# Sheet1.net
KiCad netlist of a schematic drawn in Altium Designer
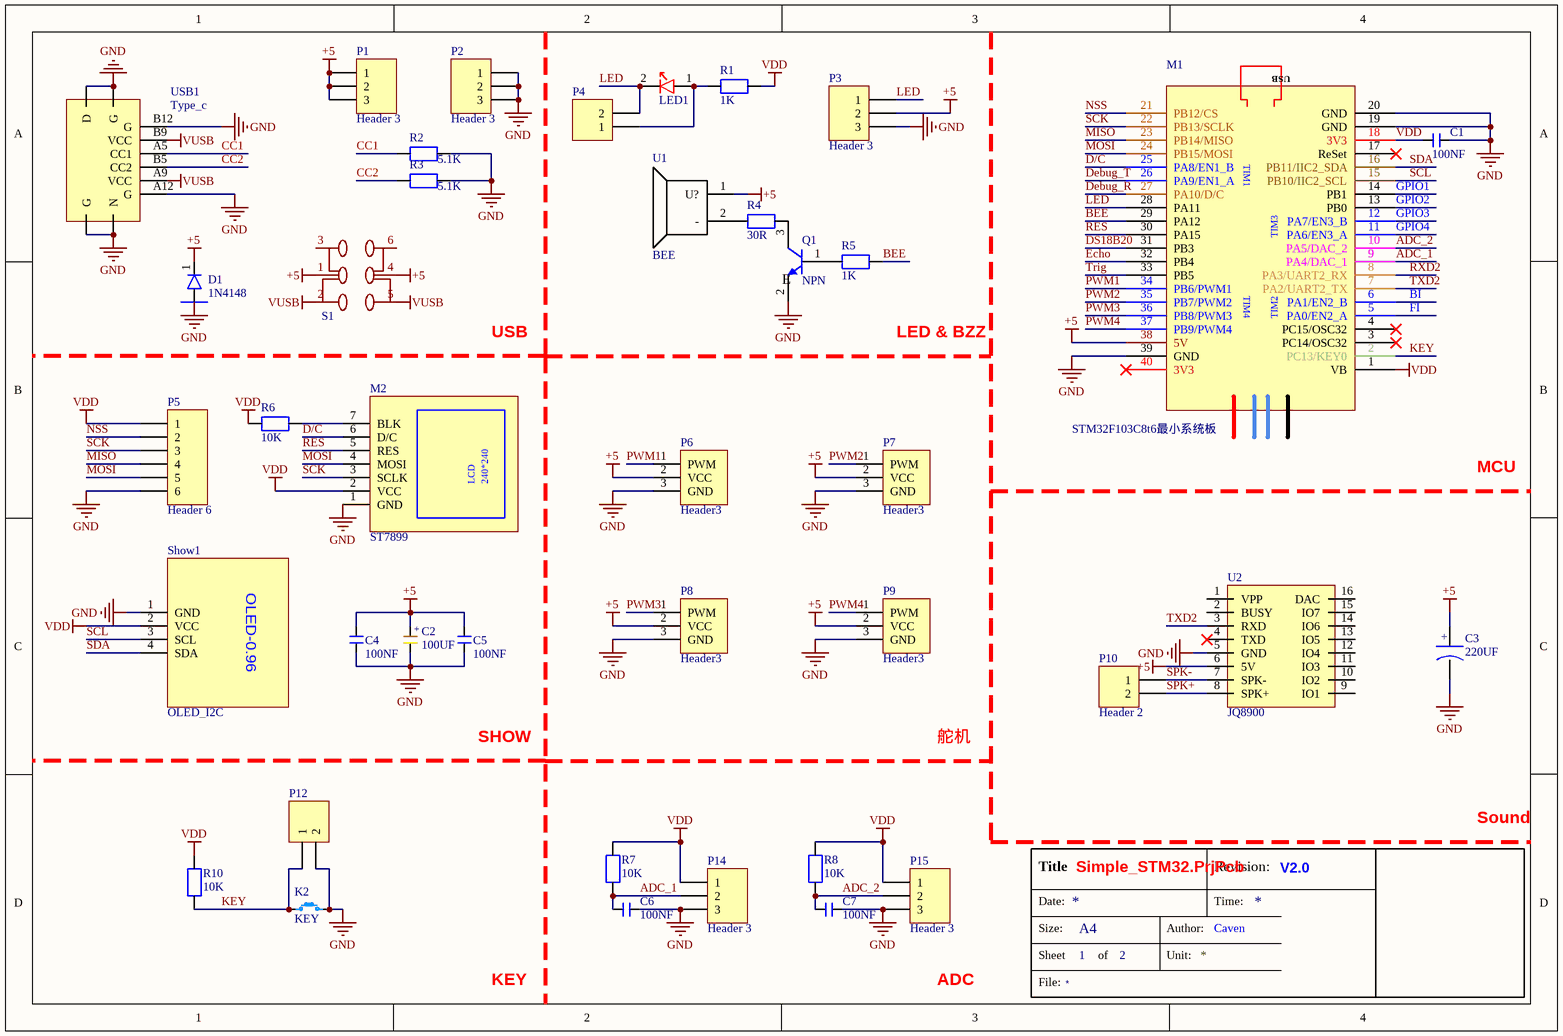
[diagram p0: Sheet1.SchDoc]

(export (version "E")
  (design (tool "Eeschema 10.0.6"))
  (components
    (comp (ref "C1")
      (value "100NF")
      (footprint "CAP_0603")
      (description "CAP  12~50V")
      (libsource (lib "User") (part "CAP"))
    )
    (comp (ref "C2")
      (value "100UF")
      (footprint "CAP_3216_A")
      (description "CAP  6~12V  钽电容")
      (libsource (lib "User") (part "CAP_TA"))
    )
    (comp (ref "C3")
      (value "220UF")
      (footprint "CAP_PR_2.5_6.3_RA")
      (description "CAP 12V ~ 50V   电解电容")
      (libsource (lib "User") (part "CAP_BIG"))
    )
    (comp (ref "C4")
      (value "100NF")
      (footprint "CAP_0603")
      (description "CAP  12~50V")
      (libsource (lib "User") (part "CAP"))
    )
    (comp (ref "C5")
      (value "100NF")
      (footprint "CAP_0603")
      (description "CAP  12~50V")
      (libsource (lib "User") (part "CAP"))
    )
    (comp (ref "C6")
      (value "100NF")
      (footprint "CAP_0603")
      (description "CAP  12~50V")
      (libsource (lib "User") (part "CAP"))
    )
    (comp (ref "C7")
      (value "100NF")
      (footprint "CAP_0603")
      (description "CAP  12~50V")
      (libsource (lib "User") (part "CAP"))
    )
    (comp (ref "D1")
      (value "1N4148")
      (footprint "Diode_DO35")
      (description "Diode_肖特基/二极管 \r\n直插")
      (libsource (lib "User") (part "Diode-DO"))
    )
    (comp (ref "K2")
      (value "KEY")
      (footprint "SW_PB_3X6")
      (description "Key")
      (libsource (lib "User") (part "KEY"))
    )
    (comp (ref "LED1")
      (value "LED_R/G/B/Y")
      (footprint "LED_5MM")
      (description "LED")
      (libsource (lib "User") (part "LED"))
    )
    (comp (ref "M1")
      (value "STM32F103C8t6最小系统板")
      (footprint "STM32F103C8_Simple")
      (description "Mode STM32F103C8t6最小系统板")
      (libsource (lib "User") (part "STM32F103C-Sys"))
    )
    (comp (ref "M2")
      (value "ST7899")
      (footprint "LCD_1.3_MODE")
      (description "SHOW")
      (libsource (lib "User") (part "LCD_TFT_1.3_MODE"))
    )
    (comp (ref "P1")
      (value "Header 3")
      (footprint "Header 2.54X3")
      (description "Header, 3-Pin")
      (fields (field (name "PUBLISHER") "Altium Limited"))
      (libsource (lib "") (part "Header 3_1"))
    )
    (comp (ref "P2")
      (value "Header 3")
      (footprint "Header 2.54X3")
      (description "Header, 3-Pin")
      (fields (field (name "PUBLISHER") "Altium Limited"))
      (libsource (lib "Miscellaneous Connectors") (part "Header 3"))
    )
    (comp (ref "P3")
      (value "Header 3")
      (footprint "XH_2.54_3P")
      (description "Header, 3-Pin")
      (fields (field (name "PUBLISHER") "Altium Limited"))
      (libsource (lib "Miscellaneous Connectors") (part "Header 3"))
    )
    (comp (ref "P4")
      (value "Header 2")
      (footprint "XH_2.54_2P")
      (description "Header, 2-Pin")
      (fields (field (name "PUBLISHER") "Altium Limited"))
      (libsource (lib "Miscellaneous Connectors") (part "Header 2"))
    )
    (comp (ref "P5")
      (value "Header 6")
      (footprint "HDR1X6")
      (description "Header, 6-Pin")
      (fields (field (name "PUBLISHER") "Altium Limited"))
      (libsource (lib "Miscellaneous Connectors") (part "Header 6"))
    )
    (comp (ref "P6")
      (value "Header3")
      (footprint "Header 2.54X3")
      (description "Header")
      (libsource (lib "User") (part "PWM_D"))
    )
    (comp (ref "P7")
      (value "Header3")
      (footprint "Header 2.54X3")
      (description "Header")
      (libsource (lib "User") (part "PWM_D"))
    )
    (comp (ref "P8")
      (value "Header3")
      (footprint "Header 2.54X3")
      (description "Header")
      (libsource (lib "User") (part "PWM_D"))
    )
    (comp (ref "P9")
      (value "Header3")
      (footprint "Header 2.54X3")
      (description "Header")
      (libsource (lib "User") (part "PWM_D"))
    )
    (comp (ref "P10")
      (value "Header 2")
      (footprint "XH2.54-WI-2P")
      (description "Header, 2-Pin")
      (fields (field (name "PUBLISHER") "Altium Limited"))
      (libsource (lib "") (part "Header 2_2"))
    )
    (comp (ref "P12")
      (value "Header 2")
      (footprint "XH_2.54_2P")
      (description "Header, 2-Pin")
      (fields (field (name "PUBLISHER") "Altium Limited"))
      (libsource (lib "") (part "Header 2_1"))
    )
    (comp (ref "P14")
      (value "Header 3")
      (footprint "HDR1X3")
      (description "Header, 3-Pin")
      (fields (field (name "PUBLISHER") "Altium Limited"))
      (libsource (lib "") (part "Header 3_1"))
    )
    (comp (ref "P15")
      (value "Header 3")
      (footprint "HDR1X3")
      (description "Header, 3-Pin")
      (fields (field (name "PUBLISHER") "Altium Limited"))
      (libsource (lib "") (part "Header 3_1"))
    )
    (comp (ref "Q1") (value "NPN") (footprint "SOT23_3") (libsource (lib "User") (part "NPN")))
    (comp (ref "R1")
      (value "1K")
      (footprint "RES_0.4_1/4W")
      (description "RES 贴片")
      (libsource (lib "User") (part "RES"))
    )
    (comp (ref "R2")
      (value "5.1K")
      (footprint "RESC_0603_2")
      (description "RES 贴片")
      (libsource (lib "User") (part "RES"))
    )
    (comp (ref "R3")
      (value "5.1K")
      (footprint "RESC_0603_2")
      (description "RES 贴片")
      (libsource (lib "User") (part "RES"))
    )
    (comp (ref "R4")
      (value "30R")
      (footprint "RES_0.4_1/4W")
      (description "RES 贴片")
      (libsource (lib "User") (part "RES"))
    )
    (comp (ref "R5")
      (value "1K")
      (footprint "RES_0.4_1/4W")
      (description "RES 贴片")
      (libsource (lib "User") (part "RES"))
    )
    (comp (ref "R6")
      (value "10K")
      (footprint "RES_0.4_1/4W")
      (description "RES 贴片")
      (libsource (lib "User") (part "RES"))
    )
    (comp (ref "R7")
      (value "10K")
      (footprint "RES_0.4_1/4W")
      (description "RES 贴片")
      (libsource (lib "User") (part "RES"))
    )
    (comp (ref "R8")
      (value "10K")
      (footprint "RES_0.4_1/4W")
      (description "RES 贴片")
      (libsource (lib "User") (part "RES"))
    )
    (comp (ref "R10")
      (value "10K")
      (footprint "RES_0.4_1/4W")
      (description "RES 贴片")
      (libsource (lib "User") (part "RES"))
    )
    (comp (ref "S1")
      (value "Switch.02")
      (footprint "SWITCH-KFC-7")
      (description "Switch")
      (libsource (lib "User") (part "Switch_2"))
    )
    (comp (ref "Show1")
      (value "OLED_I2C")
      (footprint "Header F 2.54X4")
      (description "MODE")
      (libsource (lib "User") (part "OLED_I2C"))
    )
    (comp (ref "U1") (value "BEE") (footprint "BEE-FMQ5mm") (libsource (lib "User") (part "BZZ")))
    (comp (ref "U2")
      (value "JQ8900")
      (footprint "SpkMo")
      (description "MODE")
      (libsource (lib "User") (part "SPKMO_8900"))
    )
    (comp (ref "USB1")
      (value "Type_c")
      (footprint "USB-Type-c_6P")
      (description "USB")
      (libsource (lib "User") (part "USB-Type_c-6PIn"))
    )
  )
  (nets
    (net (code "1") (name "+5") (class "Default")
      (node (ref "C2") (pin "1") (pinfunction "0_1") (pintype "passive"))
      (node (ref "C3") (pin "1") (pinfunction "0_1") (pintype "passive"))
      (node (ref "C4") (pin "2") (pinfunction "0_2") (pintype "passive"))
      (node (ref "C5") (pin "2") (pinfunction "0_2") (pintype "passive"))
      (node (ref "D1") (pin "1") (pinfunction "N_1") (pintype "passive"))
      (node (ref "M1") (pin "38") (pinfunction "5V_38") (pintype "passive"))
      (node (ref "P1") (pin "1") (pinfunction "1_1") (pintype "passive"))
      (node (ref "P1") (pin "2") (pinfunction "2_2") (pintype "passive"))
      (node (ref "P1") (pin "3") (pinfunction "3_3") (pintype "passive"))
      (node (ref "P3") (pin "2") (pinfunction "2_2") (pintype "passive"))
      (node (ref "P6") (pin "2") (pinfunction "VCC_2") (pintype "passive"))
      (node (ref "P7") (pin "2") (pinfunction "VCC_2") (pintype "passive"))
      (node (ref "P8") (pin "2") (pinfunction "VCC_2") (pintype "passive"))
      (node (ref "P9") (pin "2") (pinfunction "VCC_2") (pintype "passive"))
      (node (ref "S1") (pin "1") (pinfunction "1_1") (pintype "passive"))
      (node (ref "S1") (pin "4") (pinfunction "4_4") (pintype "passive"))
      (node (ref "U1") (pin "1") (pinfunction "U?_1") (pintype "passive"))
      (node (ref "U2") (pin "6") (pinfunction "5V_6") (pintype "passive"))
    )
    (net (code "2") (name "/ADC_1") (class "Default")
      (node (ref "C6") (pin "1") (pinfunction "0_1") (pintype "passive"))
      (node (ref "M1") (pin "9") (pinfunction "PA4/DAC_1_9") (pintype "passive"))
      (node (ref "P14") (pin "2") (pinfunction "2_2") (pintype "passive"))
      (node (ref "R7") (pin "1") (pinfunction "1_1") (pintype "passive"))
    )
    (net (code "3") (name "/ADC_2") (class "Default")
      (node (ref "C7") (pin "1") (pinfunction "0_1") (pintype "passive"))
      (node (ref "M1") (pin "10") (pinfunction "PA5/DAC_2_10") (pintype "passive"))
      (node (ref "P15") (pin "2") (pinfunction "2_2") (pintype "passive"))
      (node (ref "R8") (pin "1") (pinfunction "1_1") (pintype "passive"))
    )
    (net (code "4") (name "/BEE") (class "Default")
      (node (ref "M1") (pin "29") (pinfunction "PA12_29") (pintype "passive"))
      (node (ref "R5") (pin "1") (pinfunction "1_1") (pintype "passive"))
    )
    (net (code "5") (name "/BI") (class "Default")
      (node (ref "M1") (pin "6") (pinfunction "PA1/EN2_B_6") (pintype "passive"))
    )
    (net (code "6") (name "/CC1") (class "Default")
      (node (ref "R2") (pin "1") (pinfunction "1_1") (pintype "passive"))
      (node (ref "USB1") (pin "A5") (pinfunction "CC1_A5") (pintype "passive"))
    )
    (net (code "7") (name "/CC2") (class "Default")
      (node (ref "R3") (pin "1") (pinfunction "1_1") (pintype "passive"))
      (node (ref "USB1") (pin "B5") (pinfunction "CC2_B5") (pintype "passive"))
    )
    (net (code "8") (name "/DS18B20") (class "Default")
      (node (ref "M1") (pin "31") (pinfunction "PB3_31") (pintype "passive"))
    )
    (net (code "9") (name "/Debug_R") (class "Default")
      (node (ref "M1") (pin "27") (pinfunction "PA10/D/C_27") (pintype "passive"))
    )
    (net (code "10") (name "/Debug_T") (class "Default")
      (node (ref "M1") (pin "26") (pinfunction "PA9/EN1_A_26") (pintype "passive"))
    )
    (net (code "11") (name "/D{slash}C") (class "Default")
      (node (ref "M1") (pin "25") (pinfunction "PA8/EN1_B_25") (pintype "passive"))
      (node (ref "M2") (pin "6") (pinfunction "D/C_6") (pintype "passive"))
    )
    (net (code "12") (name "/Echo") (class "Default")
      (node (ref "M1") (pin "32") (pinfunction "PB4_32") (pintype "passive"))
    )
    (net (code "13") (name "/FI") (class "Default")
      (node (ref "M1") (pin "5") (pinfunction "PA0/EN2_A_5") (pintype "passive"))
    )
    (net (code "14") (name "/GPIO1") (class "Default")
      (node (ref "M1") (pin "14") (pinfunction "PB1_14") (pintype "passive"))
    )
    (net (code "15") (name "/GPIO2") (class "Default")
      (node (ref "M1") (pin "13") (pinfunction "PB0_13") (pintype "passive"))
    )
    (net (code "16") (name "/GPIO3") (class "Default")
      (node (ref "M1") (pin "12") (pinfunction "PA7/EN3_B_12") (pintype "passive"))
    )
    (net (code "17") (name "/GPIO4") (class "Default")
      (node (ref "M1") (pin "11") (pinfunction "PA6/EN3_A_11") (pintype "passive"))
    )
    (net (code "18") (name "/KEY") (class "Default")
      (node (ref "K2") (pin "2") (pintype "passive"))
      (node (ref "M1") (pin "2") (pinfunction "PC13/KEY0_2") (pintype "passive"))
      (node (ref "P12") (pin "1") (pinfunction "1_1") (pintype "passive"))
      (node (ref "R10") (pin "1") (pinfunction "1_1") (pintype "passive"))
    )
    (net (code "19") (name "/LED") (class "Default")
      (node (ref "LED1") (pin "2") (pinfunction "-_2") (pintype "passive"))
      (node (ref "M1") (pin "28") (pinfunction "PA11_28") (pintype "passive"))
      (node (ref "P3") (pin "1") (pinfunction "1_1") (pintype "passive"))
      (node (ref "P4") (pin "2") (pinfunction "2_2") (pintype "passive"))
    )
    (net (code "20") (name "/MISO") (class "Default")
      (node (ref "M1") (pin "23") (pinfunction "PB14/MISO_23") (pintype "passive"))
      (node (ref "P5") (pin "4") (pinfunction "4_4") (pintype "passive"))
    )
    (net (code "21") (name "/MOSI") (class "Default")
      (node (ref "M1") (pin "24") (pinfunction "PB15/MOSI_24") (pintype "passive"))
      (node (ref "M2") (pin "4") (pinfunction "MOSI_4") (pintype "passive"))
      (node (ref "P5") (pin "5") (pinfunction "5_5") (pintype "passive"))
    )
    (net (code "22") (name "/NSS") (class "Default")
      (node (ref "M1") (pin "21") (pinfunction "PB12/CS_21") (pintype "passive"))
      (node (ref "P5") (pin "2") (pinfunction "2_2") (pintype "passive"))
    )
    (net (code "23") (name "/PWM1") (class "Default")
      (node (ref "M1") (pin "34") (pinfunction "PB6/PWM1_34") (pintype "passive"))
      (node (ref "P6") (pin "1") (pinfunction "PWM_1") (pintype "passive"))
    )
    (net (code "24") (name "/PWM2") (class "Default")
      (node (ref "M1") (pin "35") (pinfunction "PB7/PWM2_35") (pintype "passive"))
      (node (ref "P7") (pin "1") (pinfunction "PWM_1") (pintype "passive"))
    )
    (net (code "25") (name "/PWM3") (class "Default")
      (node (ref "M1") (pin "36") (pinfunction "PB8/PWM3_36") (pintype "passive"))
      (node (ref "P8") (pin "1") (pinfunction "PWM_1") (pintype "passive"))
    )
    (net (code "26") (name "/PWM4") (class "Default")
      (node (ref "M1") (pin "37") (pinfunction "PB9/PWM4_37") (pintype "passive"))
      (node (ref "P9") (pin "1") (pinfunction "PWM_1") (pintype "passive"))
    )
    (net (code "27") (name "/RES") (class "Default")
      (node (ref "M1") (pin "30") (pinfunction "PA15_30") (pintype "passive"))
      (node (ref "M2") (pin "5") (pinfunction "RES_5") (pintype "passive"))
    )
    (net (code "28") (name "/RXD2") (class "Default")
      (node (ref "M1") (pin "8") (pinfunction "PA3/UART2_RX_8") (pintype "passive"))
    )
    (net (code "29") (name "/SCK") (class "Default")
      (node (ref "M1") (pin "22") (pinfunction "PB13/SCLK_22") (pintype "passive"))
      (node (ref "M2") (pin "3") (pinfunction "SCLK_3") (pintype "passive"))
      (node (ref "P5") (pin "3") (pinfunction "3_3") (pintype "passive"))
    )
    (net (code "30") (name "/SCL") (class "Default")
      (node (ref "M1") (pin "15") (pinfunction "PB10/IIC2_SCL_15") (pintype "passive"))
      (node (ref "Show1") (pin "3") (pinfunction "SCL_3") (pintype "passive"))
    )
    (net (code "31") (name "/SDA") (class "Default")
      (node (ref "M1") (pin "16") (pinfunction "PB11/IIC2_SDA_16") (pintype "passive"))
      (node (ref "Show1") (pin "4") (pinfunction "SDA_4") (pintype "passive"))
    )
    (net (code "32") (name "/SPK+") (class "Default")
      (node (ref "P10") (pin "2") (pinfunction "2_2") (pintype "passive"))
      (node (ref "U2") (pin "8") (pinfunction "SPK+_8") (pintype "passive"))
    )
    (net (code "33") (name "/SPK-") (class "Default")
      (node (ref "P10") (pin "1") (pinfunction "1_1") (pintype "passive"))
      (node (ref "U2") (pin "7") (pinfunction "SPK-_7") (pintype "passive"))
    )
    (net (code "34") (name "/TXD2") (class "Default")
      (node (ref "M1") (pin "7") (pinfunction "PA2/UART2_TX_7") (pintype "passive"))
      (node (ref "U2") (pin "3") (pinfunction "RXD_3") (pintype "passive"))
    )
    (net (code "35") (name "/Trig") (class "Default")
      (node (ref "M1") (pin "33") (pinfunction "PB5_33") (pintype "passive"))
    )
    (net (code "36") (name "GND") (class "Default")
      (node (ref "C1") (pin "1") (pinfunction "0_1") (pintype "passive"))
      (node (ref "C2") (pin "2") (pinfunction "0_2") (pintype "passive"))
      (node (ref "C3") (pin "2") (pinfunction "0_2") (pintype "passive"))
      (node (ref "C4") (pin "1") (pinfunction "0_1") (pintype "passive"))
      (node (ref "C5") (pin "1") (pinfunction "0_1") (pintype "passive"))
      (node (ref "C6") (pin "2") (pinfunction "0_2") (pintype "passive"))
      (node (ref "C7") (pin "2") (pinfunction "0_2") (pintype "passive"))
      (node (ref "D1") (pin "2") (pinfunction "P_2") (pintype "passive"))
      (node (ref "K2") (pin "1") (pintype "passive"))
      (node (ref "M1") (pin "19") (pinfunction "GND_19") (pintype "passive"))
      (node (ref "M1") (pin "20") (pinfunction "GND_20") (pintype "passive"))
      (node (ref "M1") (pin "39") (pinfunction "GND_39") (pintype "passive"))
      (node (ref "M2") (pin "1") (pinfunction "GND_1") (pintype "passive"))
      (node (ref "P12") (pin "2") (pinfunction "2_2") (pintype "passive"))
      (node (ref "P14") (pin "3") (pinfunction "3_3") (pintype "passive"))
      (node (ref "P15") (pin "3") (pinfunction "3_3") (pintype "passive"))
      (node (ref "P2") (pin "1") (pinfunction "1_1") (pintype "passive"))
      (node (ref "P2") (pin "2") (pinfunction "2_2") (pintype "passive"))
      (node (ref "P2") (pin "3") (pinfunction "3_3") (pintype "passive"))
      (node (ref "P3") (pin "3") (pinfunction "3_3") (pintype "passive"))
      (node (ref "P5") (pin "6") (pinfunction "6_6") (pintype "passive"))
      (node (ref "P6") (pin "3") (pinfunction "GND_3") (pintype "passive"))
      (node (ref "P7") (pin "3") (pinfunction "GND_3") (pintype "passive"))
      (node (ref "P8") (pin "3") (pinfunction "GND_3") (pintype "passive"))
      (node (ref "P9") (pin "3") (pinfunction "GND_3") (pintype "passive"))
      (node (ref "Q1") (pin "2") (pinfunction "E_2") (pintype "passive"))
      (node (ref "R2") (pin "2") (pinfunction "2_2") (pintype "passive"))
      (node (ref "R3") (pin "2") (pinfunction "2_2") (pintype "passive"))
      (node (ref "Show1") (pin "1") (pinfunction "GND_1") (pintype "passive"))
      (node (ref "U2") (pin "5") (pinfunction "GND_5") (pintype "passive"))
      (node (ref "USB1") (pin "A") (pinfunction "G_A") (pintype "passive"))
      (node (ref "USB1") (pin "A12") (pinfunction "G_A12") (pintype "passive"))
      (node (ref "USB1") (pin "B") (pinfunction "N_B") (pintype "passive"))
      (node (ref "USB1") (pin "B12") (pinfunction "G_B12") (pintype "passive"))
      (node (ref "USB1") (pin "C") (pinfunction "D_C") (pintype "passive"))
      (node (ref "USB1") (pin "D") (pinfunction "G_D") (pintype "passive"))
    )
    (net (code "37") (name "Net-(LED1-+)") (class "Default")
      (node (ref "LED1") (pin "1") (pinfunction "+_1") (pintype "passive"))
      (node (ref "P4") (pin "1") (pinfunction "1_1") (pintype "passive"))
      (node (ref "R1") (pin "2") (pinfunction "2_2") (pintype "passive"))
    )
    (net (code "38") (name "Net-(M2-BLK)") (class "Default")
      (node (ref "M2") (pin "7") (pinfunction "BLK_7") (pintype "passive"))
      (node (ref "R6") (pin "1") (pinfunction "1_1") (pintype "passive"))
    )
    (net (code "39") (name "Net-(Q1-B)") (class "Default")
      (node (ref "Q1") (pin "1") (pinfunction "B_1") (pintype "passive"))
      (node (ref "R5") (pin "2") (pinfunction "2_2") (pintype "passive"))
    )
    (net (code "40") (name "Net-(Q1-C)") (class "Default")
      (node (ref "Q1") (pin "3") (pinfunction "C_3") (pintype "passive"))
      (node (ref "R4") (pin "1") (pinfunction "1_1") (pintype "passive"))
    )
    (net (code "41") (name "Net-(U1--)") (class "Default")
      (node (ref "R4") (pin "2") (pinfunction "2_2") (pintype "passive"))
      (node (ref "U1") (pin "2") (pinfunction "-_2") (pintype "passive"))
    )
    (net (code "42") (name "VDD") (class "Default")
      (node (ref "C1") (pin "2") (pinfunction "0_2") (pintype "passive"))
      (node (ref "M1") (pin "1") (pinfunction "VB_1") (pintype "passive"))
      (node (ref "M1") (pin "18") (pinfunction "3V3_18") (pintype "passive"))
      (node (ref "M2") (pin "2") (pinfunction "VCC_2") (pintype "passive"))
      (node (ref "P14") (pin "1") (pinfunction "1_1") (pintype "passive"))
      (node (ref "P15") (pin "1") (pinfunction "1_1") (pintype "passive"))
      (node (ref "P5") (pin "1") (pinfunction "1_1") (pintype "passive"))
      (node (ref "R1") (pin "1") (pinfunction "1_1") (pintype "passive"))
      (node (ref "R10") (pin "2") (pinfunction "2_2") (pintype "passive"))
      (node (ref "R6") (pin "2") (pinfunction "2_2") (pintype "passive"))
      (node (ref "R7") (pin "2") (pinfunction "2_2") (pintype "passive"))
      (node (ref "R8") (pin "2") (pinfunction "2_2") (pintype "passive"))
      (node (ref "Show1") (pin "2") (pinfunction "VCC_2") (pintype "passive"))
    )
    (net (code "43") (name "VUSB") (class "Default")
      (node (ref "S1") (pin "2") (pinfunction "2_2") (pintype "passive"))
      (node (ref "S1") (pin "5") (pinfunction "5_5") (pintype "passive"))
      (node (ref "USB1") (pin "A9") (pinfunction "VCC_A9") (pintype "passive"))
      (node (ref "USB1") (pin "B9") (pinfunction "VCC_B9") (pintype "passive"))
    )
    (net (code "44") (name "unconnected-(M1-3V3-Pad40)") (class "Default")
      (node (ref "M1") (pin "40") (pinfunction "3V3_40") (pintype "passive+no_connect"))
    )
    (net (code "45") (name "unconnected-(M1-PC14{slash}OSC32-Pad3)") (class "Default")
      (node (ref "M1") (pin "3") (pinfunction "PC14/OSC32_3") (pintype "passive+no_connect"))
    )
    (net (code "46") (name "unconnected-(M1-PC15{slash}OSC32-Pad4)") (class "Default")
      (node (ref "M1") (pin "4") (pinfunction "PC15/OSC32_4") (pintype "passive+no_connect"))
    )
    (net (code "47") (name "unconnected-(M1-ReSet-Pad17)") (class "Default")
      (node (ref "M1") (pin "17") (pinfunction "ReSet_17") (pintype "passive+no_connect"))
    )
    (net (code "48") (name "unconnected-(S1-Pad3)") (class "Default")
      (node (ref "S1") (pin "3") (pinfunction "3_3") (pintype "passive"))
    )
    (net (code "49") (name "unconnected-(S1-Pad6)") (class "Default")
      (node (ref "S1") (pin "6") (pinfunction "6_6") (pintype "passive"))
    )
    (net (code "50") (name "unconnected-(U2-BUSY-Pad2)") (class "Default")
      (node (ref "U2") (pin "2") (pinfunction "BUSY_2") (pintype "passive"))
    )
    (net (code "51") (name "unconnected-(U2-DAC-Pad16)") (class "Default")
      (node (ref "U2") (pin "16") (pinfunction "DAC_16") (pintype "passive"))
    )
    (net (code "52") (name "unconnected-(U2-IO1-Pad9)") (class "Default")
      (node (ref "U2") (pin "9") (pinfunction "IO1_9") (pintype "passive"))
    )
    (net (code "53") (name "unconnected-(U2-IO2-Pad10)") (class "Default")
      (node (ref "U2") (pin "10") (pinfunction "IO2_10") (pintype "passive"))
    )
    (net (code "54") (name "unconnected-(U2-IO3-Pad11)") (class "Default")
      (node (ref "U2") (pin "11") (pinfunction "IO3_11") (pintype "passive"))
    )
    (net (code "55") (name "unconnected-(U2-IO4-Pad12)") (class "Default")
      (node (ref "U2") (pin "12") (pinfunction "IO4_12") (pintype "passive"))
    )
    (net (code "56") (name "unconnected-(U2-IO5-Pad13)") (class "Default")
      (node (ref "U2") (pin "13") (pinfunction "IO5_13") (pintype "passive"))
    )
    (net (code "57") (name "unconnected-(U2-IO6-Pad14)") (class "Default")
      (node (ref "U2") (pin "14") (pinfunction "IO6_14") (pintype "passive"))
    )
    (net (code "58") (name "unconnected-(U2-IO7-Pad15)") (class "Default")
      (node (ref "U2") (pin "15") (pinfunction "IO7_15") (pintype "passive"))
    )
    (net (code "59") (name "unconnected-(U2-TXD-Pad4)") (class "Default")
      (node (ref "U2") (pin "4") (pinfunction "TXD_4") (pintype "passive+no_connect"))
    )
    (net (code "60") (name "unconnected-(U2-VPP-Pad1)") (class "Default")
      (node (ref "U2") (pin "1") (pinfunction "VPP_1") (pintype "passive"))
    )
  )
)
